# PIR_Sensor_driver.net
KiCad netlist of a schematic drawn in Altium Designer
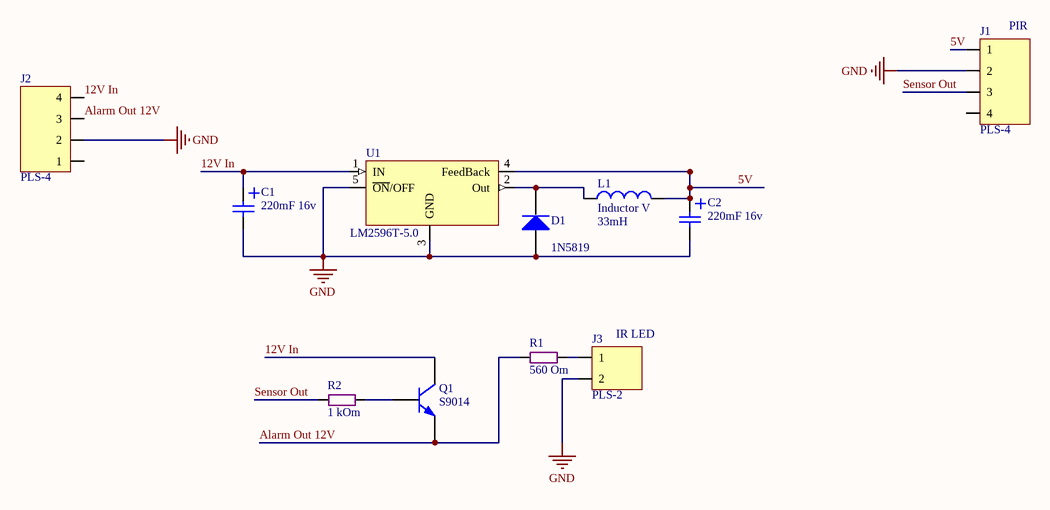
[diagram p0: PIR Sensor driver.SchDoc]

(export (version "E")
  (design (tool "Eeschema 10.0.6"))
  (components
    (comp (ref "C1")
      (value "220mF 16v")
      (footprint "Capacitor:Cap E p2mm D6.5xH11")
      (description "Capacitor")
      (libsource (lib "Capacitor") (part "Cap E 220mF x 16V"))
    )
    (comp (ref "C2")
      (value "220mF 16v")
      (footprint "Capacitor:Cap E p2mm D6.5xH11")
      (description "Capacitor")
      (libsource (lib "Capacitor") (part "Cap E 220mF x 16V"))
    )
    (comp (ref "D1")
      (value "1N5819")
      (footprint "Diodes:Diode DO-35")
      (description "1 Amp General Purpose Rectifier")
      (libsource (lib "Diodes") (part "Diode 1N5819"))
    )
    (comp (ref "J1")
      (value "PLS-4")
      (footprint "Connector:Line 2.54 X 4")
      (description "Vert, Sgl line, Male")
      (libsource (lib "") (part "PLS-4_1"))
    )
    (comp (ref "J2")
      (value "PLS-4")
      (footprint "Connector:Line 2.54 X 4")
      (description "Vert, Sgl line, Male")
      (libsource (lib "Connector") (part "PLS-4"))
    )
    (comp (ref "J3")
      (value "PLS-2")
      (footprint "Connector:Line 2.54 x 2")
      (description "Vert, Sgl line, Male")
      (libsource (lib "Connector") (part "PLS-2"))
    )
    (comp (ref "L1")
      (value "Inductor V")
      (footprint "Transformers:Toroid V D14-W6")
      (description "Inductor Vertical")
      (fields (field (name "ALTIUM_VALUE") "33mH") (field (name "PUBLISHER") "Altium Limited"))
      (libsource (lib "Transformers") (part "Inductor V"))
    )
    (comp (ref "Q1")
      (value "S9014")
      (footprint "GeneralCases:TO-92 2.54 (EBC)")
      (description "NPN Bipolar Transistor")
      (fields (field (name "PUBLISHER") "Altium Limited"))
      (libsource (lib "Transistor") (part "S9014"))
    )
    (comp (ref "R1")
      (value "560 Om")
      (footprint "PassiveComponents:Res p7.62 (4p) 0.25w")
      (libsource (lib "PassiveComponents") (part "Res Carbon"))
    )
    (comp (ref "R2")
      (value "1 kOm")
      (footprint "PassiveComponents:Res p7.62 (4p) 0.25w")
      (libsource (lib "PassiveComponents") (part "Res Carbon"))
    )
    (comp (ref "U1")
      (value "LM2596T-5.0")
      (footprint "GeneralCases:TO220-5 Horisontal")
      (description "Voltage Regulator")
      (fields (field (name "MANUFACTURER") "National Semiconductor"))
      (libsource (lib "PowerAdjusment") (part "LM2596T-5.0"))
    )
  )
  (nets
    (net (code "1") (name "/5V") (class "Default")
      (node (ref "C2") (pin "1") (pinfunction "1_1") (pintype "passive"))
      (node (ref "J1") (pin "1") (pinfunction "1_1") (pintype "passive"))
      (node (ref "L1") (pin "2") (pinfunction "2_2") (pintype "passive"))
      (node (ref "U1") (pin "4") (pinfunction "FeedBack_4") (pintype "passive"))
    )
    (net (code "2") (name "/12V In") (class "Default")
      (node (ref "C1") (pin "1") (pinfunction "1_1") (pintype "passive"))
      (node (ref "J2") (pin "4") (pinfunction "4_4") (pintype "passive"))
      (node (ref "Q1") (pin "C") (pinfunction "C_C") (pintype "passive"))
      (node (ref "U1") (pin "1") (pinfunction "IN_1") (pintype "input"))
    )
    (net (code "3") (name "/Alarm Out 12V") (class "Default")
      (node (ref "J2") (pin "3") (pinfunction "3_3") (pintype "passive"))
      (node (ref "Q1") (pin "E") (pinfunction "E_E") (pintype "passive"))
      (node (ref "R1") (pin "1") (pinfunction "1_1") (pintype "passive"))
    )
    (net (code "4") (name "/Sensor Out") (class "Default")
      (node (ref "J1") (pin "3") (pinfunction "3_3") (pintype "passive"))
      (node (ref "R2") (pin "1") (pinfunction "1_1") (pintype "passive"))
    )
    (net (code "5") (name "GND") (class "Default")
      (node (ref "C1") (pin "2") (pinfunction "2_2") (pintype "passive"))
      (node (ref "C2") (pin "2") (pinfunction "2_2") (pintype "passive"))
      (node (ref "D1") (pin "A") (pinfunction "A_A") (pintype "passive"))
      (node (ref "J1") (pin "2") (pinfunction "2_2") (pintype "passive"))
      (node (ref "J2") (pin "2") (pinfunction "2_2") (pintype "passive"))
      (node (ref "J3") (pin "2") (pinfunction "2_2") (pintype "passive"))
      (node (ref "U1") (pin "3") (pinfunction "GND_3") (pintype "passive"))
      (node (ref "U1") (pin "5") (pinfunction "~{ON}/OFF_5") (pintype "passive"))
    )
    (net (code "6") (name "Net-(J3-Pad1)") (class "Default")
      (node (ref "J3") (pin "1") (pinfunction "1_1") (pintype "passive"))
      (node (ref "R1") (pin "2") (pinfunction "2_2") (pintype "passive"))
    )
    (net (code "7") (name "Net-(Q1-PadB)") (class "Default")
      (node (ref "Q1") (pin "B") (pinfunction "B_B") (pintype "passive"))
      (node (ref "R2") (pin "2") (pinfunction "2_2") (pintype "passive"))
    )
    (net (code "8") (name "Net-(U1-Out)") (class "Default")
      (node (ref "D1") (pin "K") (pinfunction "K_K") (pintype "passive"))
      (node (ref "L1") (pin "1") (pinfunction "1_1") (pintype "passive"))
      (node (ref "U1") (pin "2") (pinfunction "Out_2") (pintype "output"))
    )
    (net (code "9") (name "unconnected-(J1-Pad4)") (class "Default")
      (node (ref "J1") (pin "4") (pinfunction "4_4") (pintype "passive"))
    )
    (net (code "10") (name "unconnected-(J2-Pad1)") (class "Default")
      (node (ref "J2") (pin "1") (pinfunction "1_1") (pintype "passive"))
    )
  )
)
